# power_v2.net
KiCad netlist of a schematic drawn in EAGLE
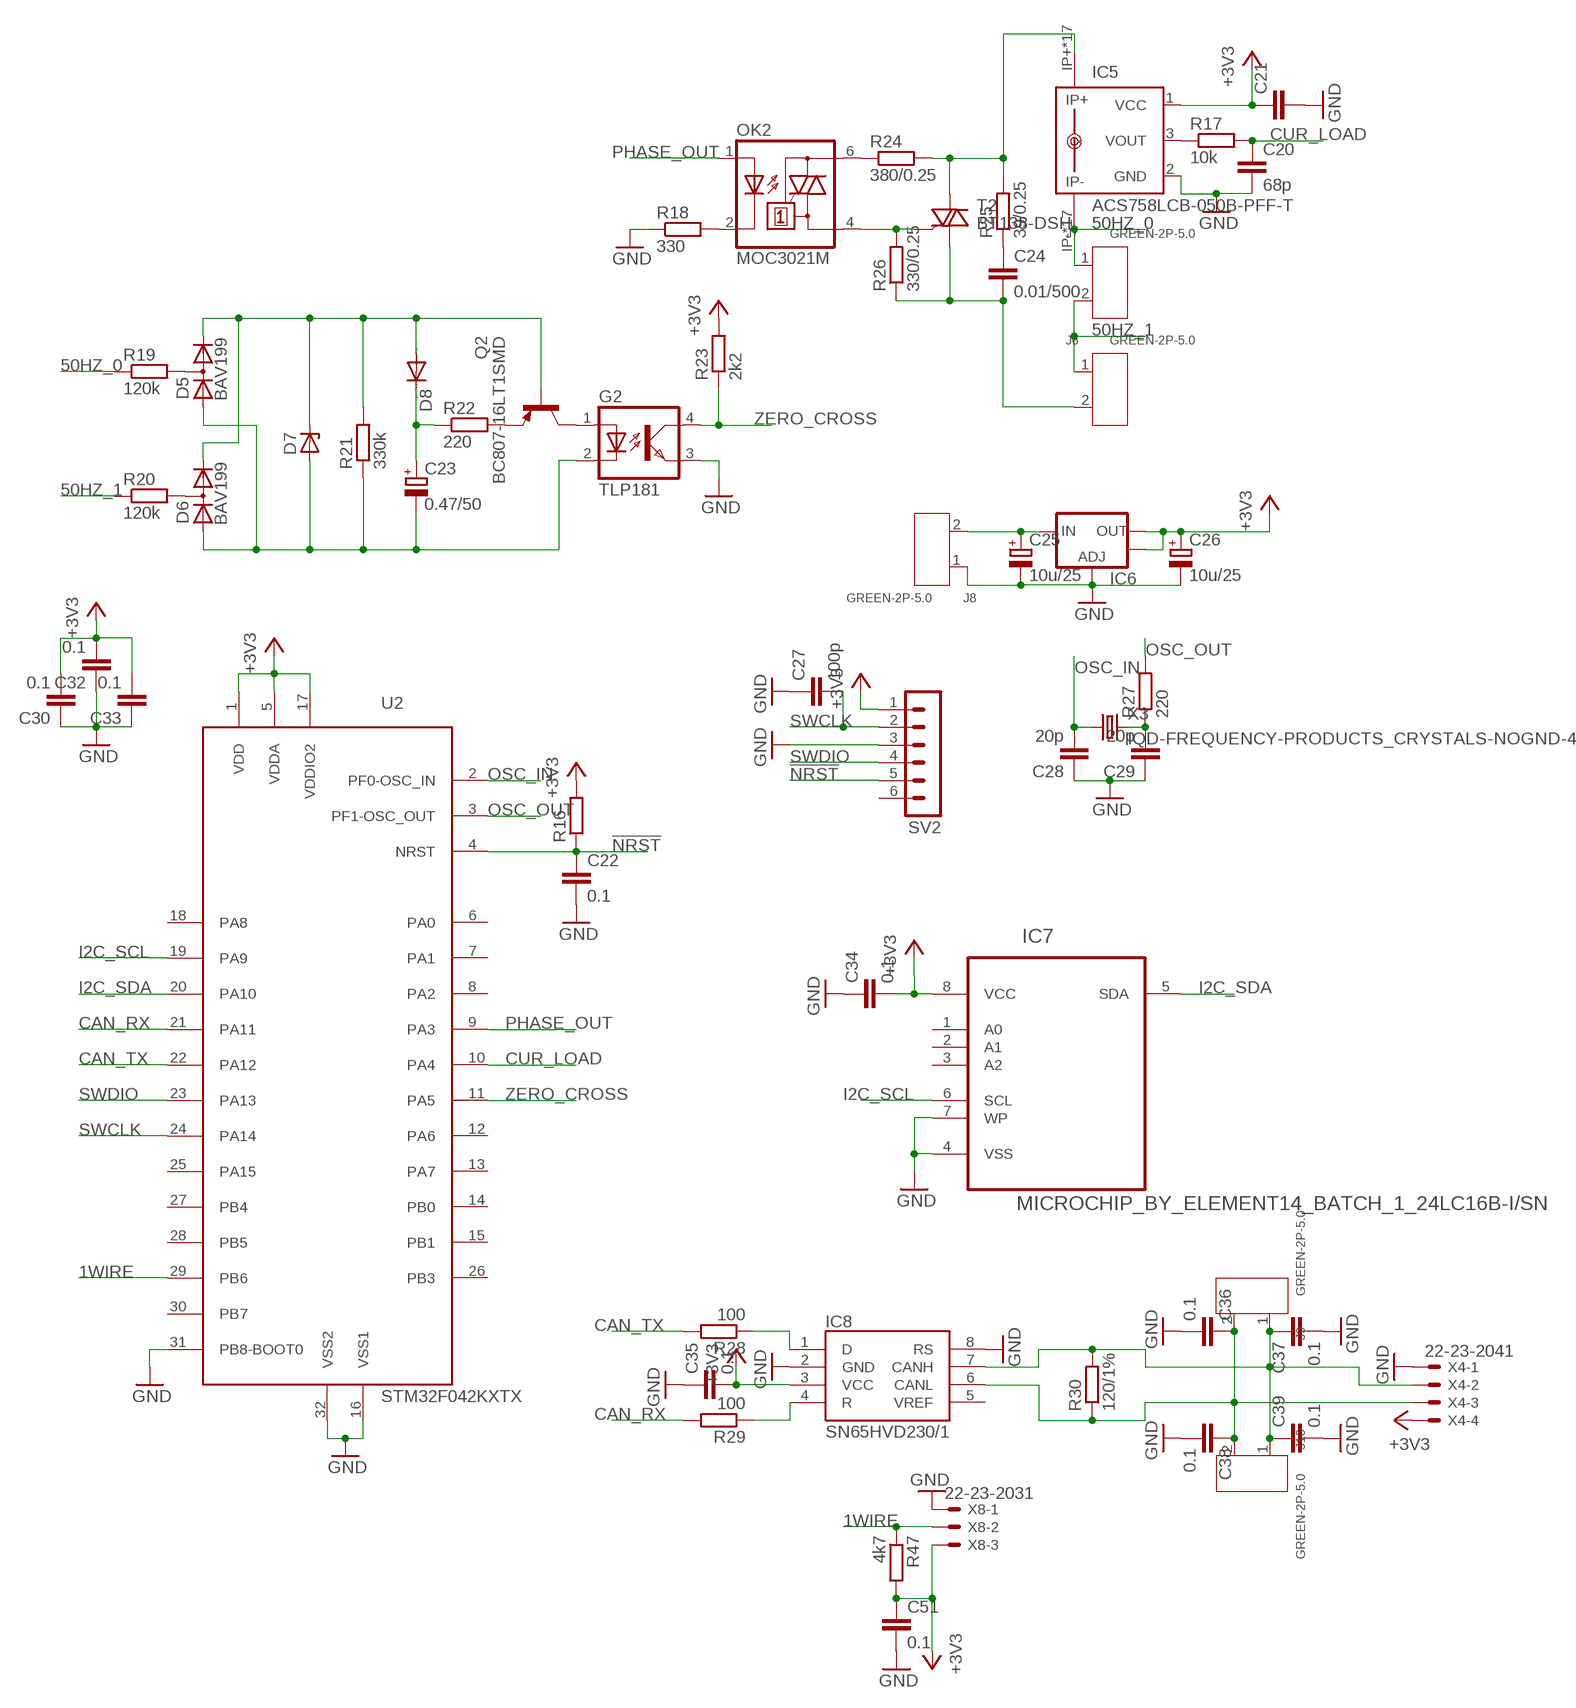
[diagram p0: schematic, sheet 1]

(export (version "E")
  (design (tool "Eeschema 10.0.6"))
  (components
    (comp (ref "C20")
      (value "68p")
      (footprint "eagle-import:C0603")
      (libsource (lib "eagle-import") (part "rcl_334_C-EUC0603"))
    )
    (comp (ref "C21")
      (value "C-EUC0603")
      (footprint "eagle-import:C0603")
      (libsource (lib "eagle-import") (part "C-EUC0603"))
    )
    (comp (ref "C22")
      (value "0.1")
      (footprint "eagle-import:C0603")
      (libsource (lib "eagle-import") (part "C-EUC0603"))
    )
    (comp (ref "C23")
      (value "0.47/50")
      (footprint "eagle-import:C_6032-28R")
      (libsource (lib "eagle-import") (part "CPOL-EUC/6032-28R"))
    )
    (comp (ref "C24")
      (value "0.01/500")
      (footprint "eagle-import:C1206")
      (libsource (lib "eagle-import") (part "C-EUC1206"))
    )
    (comp (ref "C25")
      (value "10u/25")
      (footprint "eagle-import:SMC_B")
      (libsource (lib "eagle-import") (part "CPOL-EUSMCB"))
    )
    (comp (ref "C26")
      (value "10u/25")
      (footprint "eagle-import:SMC_B")
      (libsource (lib "eagle-import") (part "CPOL-EUSMCB"))
    )
    (comp (ref "C27")
      (value "100p")
      (footprint "eagle-import:C0603")
      (libsource (lib "eagle-import") (part "C-EUC0603"))
    )
    (comp (ref "C28")
      (value "20p")
      (footprint "eagle-import:C0603")
      (libsource (lib "eagle-import") (part "C-EUC0603"))
    )
    (comp (ref "C29")
      (value "20p")
      (footprint "eagle-import:C0603")
      (libsource (lib "eagle-import") (part "C-EUC0603"))
    )
    (comp (ref "C30")
      (value "0.1")
      (footprint "eagle-import:C0603")
      (libsource (lib "eagle-import") (part "rcl_334_C-EUC0603"))
    )
    (comp (ref "C32")
      (value "0.1")
      (footprint "eagle-import:C0603")
      (libsource (lib "eagle-import") (part "C-EUC0603"))
    )
    (comp (ref "C33")
      (value "0.1")
      (footprint "eagle-import:C0603")
      (libsource (lib "eagle-import") (part "C-EUC0603"))
    )
    (comp (ref "C34")
      (value "0.1")
      (footprint "eagle-import:C0603")
      (libsource (lib "eagle-import") (part "C-EUC0603"))
    )
    (comp (ref "C35")
      (value "0.1")
      (footprint "eagle-import:C0603")
      (libsource (lib "eagle-import") (part "C-EUC0603"))
    )
    (comp (ref "C36")
      (value "0.1")
      (footprint "eagle-import:C0603")
      (libsource (lib "eagle-import") (part "C-EUC0603"))
    )
    (comp (ref "C37")
      (value "0.1")
      (footprint "eagle-import:C0603")
      (libsource (lib "eagle-import") (part "C-EUC0603"))
    )
    (comp (ref "C38")
      (value "0.1")
      (footprint "eagle-import:C0603")
      (libsource (lib "eagle-import") (part "C-EUC0603"))
    )
    (comp (ref "C39")
      (value "0.1")
      (footprint "eagle-import:C0603")
      (libsource (lib "eagle-import") (part "C-EUC0603"))
    )
    (comp (ref "C51")
      (value "0.1")
      (footprint "eagle-import:C0603")
      (libsource (lib "eagle-import") (part "C-EUC0603"))
    )
    (comp (ref "D5")
      (value "BAV199")
      (footprint "eagle-import:SOT23")
      (libsource (lib "eagle-import") (part "BAV199"))
    )
    (comp (ref "D6")
      (value "BAV199")
      (footprint "eagle-import:SOT23")
      (libsource (lib "eagle-import") (part "BAV199"))
    )
    (comp (ref "D7")
      (value "ZENER-DIODESOD80C")
      (footprint "eagle-import:SOD80C")
      (libsource (lib "eagle-import") (part "ZENER-DIODESOD80C"))
    )
    (comp (ref "D8")
      (value "DIODE-SOD523")
      (footprint "eagle-import:SOD523")
      (libsource (lib "eagle-import") (part "DIODE-SOD523"))
    )
    (comp (ref "G2")
      (value "TLP181")
      (footprint "eagle-import:SOP04")
      (libsource (lib "eagle-import") (part "TLP181"))
    )
    (comp (ref "IC5")
      (value "ACS758LCB-050B-PFF-T")
      (footprint "eagle-import:CB-PFF")
      (libsource (lib "eagle-import") (part "ACS758LCB-050B-PFF-T"))
    )
    (comp (ref "IC6")
      (value "V_REG_LM1117SOT223")
      (footprint "eagle-import:SOT223")
      (libsource (lib "eagle-import") (part "V_REG_LM1117SOT223"))
    )
    (comp (ref "IC7")
      (value "MICROCHIP_BY_ELEMENT14_BATCH_1_24LC16B-I/SN")
      (footprint "eagle-import:MICROCHIP_BY_ELEMENT14_BATCH_1_SOIC127P600X175-8N")
      (fields (field (name "MPN") "24LC16B-I/SN"))
      (libsource (lib "eagle-import") (part "MICROCHIP_BY_ELEMENT14_BATCH_1_24LC16B-I/SN"))
    )
    (comp (ref "IC8")
      (value "SN65HVD230/1")
      (footprint "eagle-import:SO8")
      (libsource (lib "eagle-import") (part "SN65HVD230/1"))
    )
    (comp (ref "J6")
      (value "GREEN-2P-5.0")
      (footprint "eagle-import:H2-5.0-10.5X8.0MM")
      (libsource (lib "eagle-import") (part "SCREW-TERMINAL-GREEN(2P-5.0)"))
    )
    (comp (ref "J7")
      (value "GREEN-2P-5.0")
      (footprint "eagle-import:H2-5.0-10.5X8.0MM")
      (libsource (lib "eagle-import") (part "SCREW-TERMINAL-GREEN(2P-5.0)"))
    )
    (comp (ref "J8")
      (value "GREEN-2P-5.0")
      (footprint "eagle-import:H2-5.0-10.5X8.0MM")
      (libsource (lib "eagle-import") (part "SCREW-TERMINAL-GREEN(2P-5.0)"))
    )
    (comp (ref "J9")
      (value "GREEN-2P-5.0")
      (footprint "eagle-import:H2-5.0-10.5X8.0MM")
      (libsource (lib "eagle-import") (part "SCREW-TERMINAL-GREEN(2P-5.0)"))
    )
    (comp (ref "J10")
      (value "GREEN-2P-5.0")
      (footprint "eagle-import:H2-5.0-10.5X8.0MM")
      (libsource (lib "eagle-import") (part "SCREW-TERMINAL-GREEN(2P-5.0)"))
    )
    (comp (ref "OK2")
      (value "MOC3021M")
      (footprint "eagle-import:DIL06")
      (fields (field (name "MF") "FAIRCHILD SEMICONDUCTOR") (field (name "MPN") "MOC3021-M"))
      (libsource (lib "eagle-import") (part "MOC30M21"))
    )
    (comp (ref "Q2")
      (value "BC807-16LT1SMD")
      (footprint "eagle-import:SOT23-BEC")
      (libsource (lib "eagle-import") (part "BC807SMD-16LT1"))
    )
    (comp (ref "R16")
      (value "R-EU_R0603")
      (footprint "eagle-import:R0603")
      (libsource (lib "eagle-import") (part "R-EU_R0603"))
    )
    (comp (ref "R17")
      (value "10k")
      (footprint "eagle-import:R0603")
      (libsource (lib "eagle-import") (part "R-EU_R0603"))
    )
    (comp (ref "R18")
      (value "330")
      (footprint "eagle-import:R0603")
      (libsource (lib "eagle-import") (part "rcl_334_R-EU_R0603"))
    )
    (comp (ref "R19")
      (value "120k")
      (footprint "eagle-import:R1206")
      (libsource (lib "eagle-import") (part "R-EU_R1206"))
    )
    (comp (ref "R20")
      (value "120k")
      (footprint "eagle-import:R1206")
      (libsource (lib "eagle-import") (part "R-EU_R1206"))
    )
    (comp (ref "R21")
      (value "330k")
      (footprint "eagle-import:R1206")
      (libsource (lib "eagle-import") (part "R-EU_R1206"))
    )
    (comp (ref "R22")
      (value "220")
      (footprint "eagle-import:R1206")
      (libsource (lib "eagle-import") (part "R-EU_R1206"))
    )
    (comp (ref "R23")
      (value "2k2")
      (footprint "eagle-import:R0603")
      (libsource (lib "eagle-import") (part "R-EU_R0603"))
    )
    (comp (ref "R24")
      (value "380/0.25")
      (footprint "eagle-import:M1206")
      (libsource (lib "eagle-import") (part "R-EU_M1206"))
    )
    (comp (ref "R25")
      (value "39/0.25")
      (footprint "eagle-import:M1206")
      (libsource (lib "eagle-import") (part "R-EU_M1206"))
    )
    (comp (ref "R26")
      (value "330/0.25")
      (footprint "eagle-import:M1206")
      (libsource (lib "eagle-import") (part "R-EU_M1206"))
    )
    (comp (ref "R27")
      (value "220")
      (footprint "eagle-import:R0603")
      (libsource (lib "eagle-import") (part "R-EU_R0603"))
    )
    (comp (ref "R28")
      (value "100")
      (footprint "eagle-import:R0603")
      (libsource (lib "eagle-import") (part "rcl_334_R-EU_R0603"))
    )
    (comp (ref "R29")
      (value "100")
      (footprint "eagle-import:R0603")
      (libsource (lib "eagle-import") (part "R-EU_R0603"))
    )
    (comp (ref "R30")
      (value "120/1%")
      (footprint "eagle-import:R0603")
      (libsource (lib "eagle-import") (part "R-EU_R0603"))
    )
    (comp (ref "R47")
      (value "4k7")
      (footprint "eagle-import:R0603")
      (libsource (lib "eagle-import") (part "rcl_334_R-EU_R0603"))
    )
    (comp (ref "SV2")
      (value "CON-LSTB_MA06-1")
      (footprint "eagle-import:CON-LSTB_MA06-1")
      (libsource (lib "eagle-import") (part "CON-LSTB_MA06-1"))
    )
    (comp (ref "T2")
      (value "BT138-DSH")
      (footprint "eagle-import:TO220DSH")
      (libsource (lib "eagle-import") (part "BT138-DSH"))
    )
    (comp (ref "U2")
      (value "STM32F042KXTX")
      (footprint "eagle-import:LQFP32")
      (libsource (lib "eagle-import") (part "STM32F042KXTX"))
    )
    (comp (ref "X3")
      (value "IQD-FREQUENCY-PRODUCTS_CRYSTALS-NOGND-4-HSMX")
      (footprint "eagle-import:IQD-FREQUENCY-PRODUCTS_HC49-4-HSMX")
      (libsource (lib "eagle-import") (part "IQD-FREQUENCY-PRODUCTS_CRYSTALS-NOGND-4-HSMX"))
    )
    (comp (ref "X4")
      (value "22-23-2041")
      (footprint "eagle-import:22-23-2041")
      (fields (field (name "MF") "MOLEX"))
      (libsource (lib "eagle-import") (part "22-23-2041"))
    )
    (comp (ref "X8")
      (value "22-23-2031")
      (footprint "eagle-import:22-23-2031")
      (fields (field (name "MF") "MOLEX"))
      (libsource (lib "eagle-import") (part "22-23-2031"))
    )
  )
  (nets
    (net (code "1") (name "+3V3") (class "Default")
      (node (ref "C21") (pin "1") (pinfunction "1_1") (pintype "passive"))
      (node (ref "C26") (pin "+") (pinfunction "+_+") (pintype "passive"))
      (node (ref "C30") (pin "2") (pinfunction "2_2") (pintype "passive"))
      (node (ref "C32") (pin "2") (pinfunction "2_2") (pintype "passive"))
      (node (ref "C33") (pin "2") (pinfunction "2_2") (pintype "passive"))
      (node (ref "C34") (pin "2") (pinfunction "2_2") (pintype "passive"))
      (node (ref "C35") (pin "2") (pinfunction "2_2") (pintype "passive"))
      (node (ref "C51") (pin "1") (pinfunction "1_1") (pintype "passive"))
      (node (ref "IC5") (pin "1") (pinfunction "VCC_1") (pintype "power_in"))
      (node (ref "IC6") (pin "2") (pinfunction "OUT_2") (pintype "output"))
      (node (ref "IC6") (pin "4") (pinfunction "OUT_4") (pintype "output"))
      (node (ref "IC7") (pin "8") (pinfunction "VCC_8") (pintype "power_in"))
      (node (ref "IC8") (pin "3") (pinfunction "VCC_3") (pintype "power_in"))
      (node (ref "R16") (pin "2") (pinfunction "2_2") (pintype "passive"))
      (node (ref "R23") (pin "2") (pinfunction "2_2") (pintype "passive"))
      (node (ref "R47") (pin "2") (pinfunction "2_2") (pintype "passive"))
      (node (ref "SV2") (pin "1") (pinfunction "1_1") (pintype "passive"))
      (node (ref "U2") (pin "1") (pinfunction "VDD_1") (pintype "bidirectional"))
      (node (ref "U2") (pin "17") (pinfunction "VDDIO2_17") (pintype "bidirectional"))
      (node (ref "U2") (pin "5") (pinfunction "VDDA_5") (pintype "bidirectional"))
      (node (ref "X4") (pin "4") (pinfunction "S_4") (pintype "passive"))
      (node (ref "X8") (pin "3") (pinfunction "S_3") (pintype "passive"))
    )
    (net (code "2") (name "/1WIRE") (class "Default")
      (node (ref "R47") (pin "1") (pinfunction "1_1") (pintype "passive"))
      (node (ref "U2") (pin "29") (pinfunction "PB6_29") (pintype "bidirectional"))
      (node (ref "X8") (pin "2") (pinfunction "S_2") (pintype "passive"))
    )
    (net (code "3") (name "/50HZ_0") (class "Default")
      (node (ref "IC5") (pin "IP-") (pinfunction "IP-_IP-") (pintype "passive"))
      (node (ref "IC5") (pin "IP-@10") (pinfunction "IP-_IP-@10") (pintype "passive"))
      (node (ref "IC5") (pin "IP-@11") (pinfunction "IP-_IP-@11") (pintype "passive"))
      (node (ref "IC5") (pin "IP-@12") (pinfunction "IP-_IP-@12") (pintype "passive"))
      (node (ref "IC5") (pin "IP-@13") (pinfunction "IP-_IP-@13") (pintype "passive"))
      (node (ref "IC5") (pin "IP-@14") (pinfunction "IP-_IP-@14") (pintype "passive"))
      (node (ref "IC5") (pin "IP-@15") (pinfunction "IP-_IP-@15") (pintype "passive"))
      (node (ref "IC5") (pin "IP-@16") (pinfunction "IP-_IP-@16") (pintype "passive"))
      (node (ref "IC5") (pin "IP-@17") (pinfunction "IP-_IP-@17") (pintype "passive"))
      (node (ref "IC5") (pin "IP-@2") (pinfunction "IP-_IP-@2") (pintype "passive"))
      (node (ref "IC5") (pin "IP-@3") (pinfunction "IP-_IP-@3") (pintype "passive"))
      (node (ref "IC5") (pin "IP-@4") (pinfunction "IP-_IP-@4") (pintype "passive"))
      (node (ref "IC5") (pin "IP-@5") (pinfunction "IP-_IP-@5") (pintype "passive"))
      (node (ref "IC5") (pin "IP-@6") (pinfunction "IP-_IP-@6") (pintype "passive"))
      (node (ref "IC5") (pin "IP-@7") (pinfunction "IP-_IP-@7") (pintype "passive"))
      (node (ref "IC5") (pin "IP-@8") (pinfunction "IP-_IP-@8") (pintype "passive"))
      (node (ref "IC5") (pin "IP-@9") (pinfunction "IP-_IP-@9") (pintype "passive"))
      (node (ref "J7") (pin "1") (pinfunction "1_1") (pintype "bidirectional"))
      (node (ref "R19") (pin "1") (pinfunction "1_1") (pintype "passive"))
    )
    (net (code "4") (name "/50HZ_1") (class "Default")
      (node (ref "J6") (pin "1") (pinfunction "1_1") (pintype "bidirectional"))
      (node (ref "J7") (pin "2") (pinfunction "2_2") (pintype "bidirectional"))
      (node (ref "R20") (pin "1") (pinfunction "1_1") (pintype "passive"))
    )
    (net (code "5") (name "/CAN_RX") (class "Default")
      (node (ref "R29") (pin "2") (pinfunction "2_2") (pintype "passive"))
      (node (ref "U2") (pin "21") (pinfunction "PA11_21") (pintype "bidirectional"))
    )
    (net (code "6") (name "/CAN_TX") (class "Default")
      (node (ref "R28") (pin "2") (pinfunction "2_2") (pintype "passive"))
      (node (ref "U2") (pin "22") (pinfunction "PA12_22") (pintype "bidirectional"))
    )
    (net (code "7") (name "/CUR_LOAD") (class "Default")
      (node (ref "C20") (pin "1") (pinfunction "1_1") (pintype "passive"))
      (node (ref "R17") (pin "2") (pinfunction "2_2") (pintype "passive"))
      (node (ref "U2") (pin "10") (pinfunction "PA4_10") (pintype "bidirectional"))
    )
    (net (code "8") (name "/I2C_SCL") (class "Default")
      (node (ref "IC7") (pin "6") (pinfunction "SCL_6") (pintype "input"))
      (node (ref "U2") (pin "19") (pinfunction "PA9_19") (pintype "bidirectional"))
    )
    (net (code "9") (name "/I2C_SDA") (class "Default")
      (node (ref "IC7") (pin "5") (pinfunction "SDA_5") (pintype "bidirectional"))
      (node (ref "U2") (pin "20") (pinfunction "PA10_20") (pintype "bidirectional"))
    )
    (net (code "10") (name "/OSC_IN") (class "Default")
      (node (ref "C28") (pin "2") (pinfunction "2_2") (pintype "passive"))
      (node (ref "U2") (pin "2") (pinfunction "PF0-OSC_IN_2") (pintype "bidirectional"))
      (node (ref "X3") (pin "1") (pinfunction "1_1") (pintype "passive"))
    )
    (net (code "11") (name "/OSC_OUT") (class "Default")
      (node (ref "R27") (pin "2") (pinfunction "2_2") (pintype "passive"))
      (node (ref "U2") (pin "3") (pinfunction "PF1-OSC_OUT_3") (pintype "bidirectional"))
    )
    (net (code "12") (name "/PHASE_OUT") (class "Default")
      (node (ref "OK2") (pin "1") (pinfunction "A_1") (pintype "passive"))
      (node (ref "U2") (pin "9") (pinfunction "PA3_9") (pintype "bidirectional"))
    )
    (net (code "13") (name "/SWCLK") (class "Default")
      (node (ref "C27") (pin "2") (pinfunction "2_2") (pintype "passive"))
      (node (ref "SV2") (pin "2") (pinfunction "2_2") (pintype "passive"))
      (node (ref "U2") (pin "24") (pinfunction "PA14_24") (pintype "bidirectional"))
    )
    (net (code "14") (name "/SWDIO") (class "Default")
      (node (ref "SV2") (pin "4") (pinfunction "4_4") (pintype "passive"))
      (node (ref "U2") (pin "23") (pinfunction "PA13_23") (pintype "bidirectional"))
    )
    (net (code "15") (name "/ZERO_CROSS") (class "Default")
      (node (ref "G2") (pin "4") (pinfunction "COL_4") (pintype "passive"))
      (node (ref "R23") (pin "1") (pinfunction "1_1") (pintype "passive"))
      (node (ref "U2") (pin "11") (pinfunction "PA5_11") (pintype "bidirectional"))
    )
    (net (code "16") (name "/~{NRST}") (class "Default")
      (node (ref "C22") (pin "1") (pinfunction "1_1") (pintype "passive"))
      (node (ref "R16") (pin "1") (pinfunction "1_1") (pintype "passive"))
      (node (ref "SV2") (pin "5") (pinfunction "5_5") (pintype "passive"))
      (node (ref "U2") (pin "4") (pinfunction "NRST_4") (pintype "bidirectional"))
    )
    (net (code "17") (name "GND") (class "Default")
      (node (ref "C20") (pin "2") (pinfunction "2_2") (pintype "passive"))
      (node (ref "C21") (pin "2") (pinfunction "2_2") (pintype "passive"))
      (node (ref "C22") (pin "2") (pinfunction "2_2") (pintype "passive"))
      (node (ref "C25") (pin "-") (pinfunction "-_-") (pintype "passive"))
      (node (ref "C26") (pin "-") (pinfunction "-_-") (pintype "passive"))
      (node (ref "C27") (pin "1") (pinfunction "1_1") (pintype "passive"))
      (node (ref "C28") (pin "1") (pinfunction "1_1") (pintype "passive"))
      (node (ref "C29") (pin "1") (pinfunction "1_1") (pintype "passive"))
      (node (ref "C30") (pin "1") (pinfunction "1_1") (pintype "passive"))
      (node (ref "C32") (pin "1") (pinfunction "1_1") (pintype "passive"))
      (node (ref "C33") (pin "1") (pinfunction "1_1") (pintype "passive"))
      (node (ref "C34") (pin "1") (pinfunction "1_1") (pintype "passive"))
      (node (ref "C35") (pin "1") (pinfunction "1_1") (pintype "passive"))
      (node (ref "C36") (pin "2") (pinfunction "2_2") (pintype "passive"))
      (node (ref "C37") (pin "2") (pinfunction "2_2") (pintype "passive"))
      (node (ref "C38") (pin "2") (pinfunction "2_2") (pintype "passive"))
      (node (ref "C39") (pin "2") (pinfunction "2_2") (pintype "passive"))
      (node (ref "C51") (pin "2") (pinfunction "2_2") (pintype "passive"))
      (node (ref "G2") (pin "3") (pinfunction "EMIT_3") (pintype "passive"))
      (node (ref "IC5") (pin "2") (pinfunction "GND_2") (pintype "power_in"))
      (node (ref "IC6") (pin "1") (pinfunction "ADJ_1") (pintype "input"))
      (node (ref "IC7") (pin "4") (pinfunction "VSS_4") (pintype "passive"))
      (node (ref "IC7") (pin "7") (pinfunction "WP_7") (pintype "input"))
      (node (ref "IC8") (pin "2") (pinfunction "GND_2") (pintype "power_in"))
      (node (ref "IC8") (pin "8") (pinfunction "RS_8") (pintype "bidirectional"))
      (node (ref "J8") (pin "1") (pinfunction "1_1") (pintype "bidirectional"))
      (node (ref "R18") (pin "1") (pinfunction "1_1") (pintype "passive"))
      (node (ref "SV2") (pin "3") (pinfunction "3_3") (pintype "passive"))
      (node (ref "U2") (pin "16") (pinfunction "VSS1_16") (pintype "bidirectional"))
      (node (ref "U2") (pin "31") (pinfunction "PB8-BOOT0_31") (pintype "bidirectional"))
      (node (ref "U2") (pin "32") (pinfunction "VSS2_32") (pintype "bidirectional"))
      (node (ref "X4") (pin "1") (pinfunction "S_1") (pintype "passive"))
      (node (ref "X8") (pin "1") (pinfunction "S_1") (pintype "passive"))
    )
    (net (code "18") (name "Net-(C23-Pad+)") (class "Default")
      (node (ref "C23") (pin "+") (pinfunction "+_+") (pintype "passive"))
      (node (ref "D8") (pin "C") (pinfunction "C_C") (pintype "passive"))
      (node (ref "R22") (pin "1") (pinfunction "1_1") (pintype "passive"))
    )
    (net (code "19") (name "Net-(C24-Pad1)") (class "Default")
      (node (ref "C24") (pin "1") (pinfunction "1_1") (pintype "passive"))
      (node (ref "R25") (pin "1") (pinfunction "1_1") (pintype "passive"))
    )
    (net (code "20") (name "Net-(C24-Pad2)") (class "Default")
      (node (ref "C24") (pin "2") (pinfunction "2_2") (pintype "passive"))
      (node (ref "J6") (pin "2") (pinfunction "2_2") (pintype "bidirectional"))
      (node (ref "R26") (pin "1") (pinfunction "1_1") (pintype "passive"))
      (node (ref "T2") (pin "A1") (pinfunction "A1_A1") (pintype "passive"))
    )
    (net (code "21") (name "Net-(C29-Pad2)") (class "Default")
      (node (ref "C29") (pin "2") (pinfunction "2_2") (pintype "passive"))
      (node (ref "R27") (pin "1") (pinfunction "1_1") (pintype "passive"))
      (node (ref "X3") (pin "2") (pinfunction "2_2") (pintype "passive"))
    )
    (net (code "22") (name "Net-(D5-A)") (class "Default")
      (node (ref "C23") (pin "-") (pinfunction "-_-") (pintype "passive"))
      (node (ref "D5") (pin "1") (pinfunction "A_1") (pintype "passive"))
      (node (ref "D6") (pin "1") (pinfunction "A_1") (pintype "passive"))
      (node (ref "D7") (pin "A") (pinfunction "A_A") (pintype "passive"))
      (node (ref "G2") (pin "2") (pinfunction "C_2") (pintype "passive"))
      (node (ref "R21") (pin "1") (pinfunction "1_1") (pintype "passive"))
    )
    (net (code "23") (name "Net-(D5-AC)") (class "Default")
      (node (ref "D5") (pin "3") (pinfunction "AC_3") (pintype "passive"))
      (node (ref "R19") (pin "2") (pinfunction "2_2") (pintype "passive"))
    )
    (net (code "24") (name "Net-(D5-C)") (class "Default")
      (node (ref "D5") (pin "2") (pinfunction "C_2") (pintype "passive"))
      (node (ref "D6") (pin "2") (pinfunction "C_2") (pintype "passive"))
      (node (ref "D7") (pin "C") (pinfunction "C_C") (pintype "passive"))
      (node (ref "D8") (pin "A") (pinfunction "A_A") (pintype "passive"))
      (node (ref "Q2") (pin "B") (pinfunction "B_B") (pintype "passive"))
      (node (ref "R21") (pin "2") (pinfunction "2_2") (pintype "passive"))
    )
    (net (code "25") (name "Net-(D6-AC)") (class "Default")
      (node (ref "D6") (pin "3") (pinfunction "AC_3") (pintype "passive"))
      (node (ref "R20") (pin "2") (pinfunction "2_2") (pintype "passive"))
    )
    (net (code "26") (name "Net-(G2-A)") (class "Default")
      (node (ref "G2") (pin "1") (pinfunction "A_1") (pintype "passive"))
      (node (ref "Q2") (pin "C") (pinfunction "C_C") (pintype "passive"))
    )
    (net (code "27") (name "Net-(IC5-IP+-PadIP+@10)") (class "Default")
      (node (ref "IC5") (pin "IP+") (pinfunction "IP+_IP+") (pintype "passive"))
      (node (ref "IC5") (pin "IP+@10") (pinfunction "IP+_IP+@10") (pintype "passive"))
      (node (ref "IC5") (pin "IP+@11") (pinfunction "IP+_IP+@11") (pintype "passive"))
      (node (ref "IC5") (pin "IP+@12") (pinfunction "IP+_IP+@12") (pintype "passive"))
      (node (ref "IC5") (pin "IP+@13") (pinfunction "IP+_IP+@13") (pintype "passive"))
      (node (ref "IC5") (pin "IP+@14") (pinfunction "IP+_IP+@14") (pintype "passive"))
      (node (ref "IC5") (pin "IP+@15") (pinfunction "IP+_IP+@15") (pintype "passive"))
      (node (ref "IC5") (pin "IP+@16") (pinfunction "IP+_IP+@16") (pintype "passive"))
      (node (ref "IC5") (pin "IP+@17") (pinfunction "IP+_IP+@17") (pintype "passive"))
      (node (ref "IC5") (pin "IP+@2") (pinfunction "IP+_IP+@2") (pintype "passive"))
      (node (ref "IC5") (pin "IP+@3") (pinfunction "IP+_IP+@3") (pintype "passive"))
      (node (ref "IC5") (pin "IP+@4") (pinfunction "IP+_IP+@4") (pintype "passive"))
      (node (ref "IC5") (pin "IP+@5") (pinfunction "IP+_IP+@5") (pintype "passive"))
      (node (ref "IC5") (pin "IP+@6") (pinfunction "IP+_IP+@6") (pintype "passive"))
      (node (ref "IC5") (pin "IP+@7") (pinfunction "IP+_IP+@7") (pintype "passive"))
      (node (ref "IC5") (pin "IP+@8") (pinfunction "IP+_IP+@8") (pintype "passive"))
      (node (ref "IC5") (pin "IP+@9") (pinfunction "IP+_IP+@9") (pintype "passive"))
      (node (ref "R24") (pin "2") (pinfunction "2_2") (pintype "passive"))
      (node (ref "R25") (pin "2") (pinfunction "2_2") (pintype "passive"))
      (node (ref "T2") (pin "A2") (pinfunction "A2_A2") (pintype "passive"))
    )
    (net (code "28") (name "Net-(IC5-VOUT)") (class "Default")
      (node (ref "IC5") (pin "3") (pinfunction "VOUT_3") (pintype "output"))
      (node (ref "R17") (pin "1") (pinfunction "1_1") (pintype "passive"))
    )
    (net (code "29") (name "Net-(IC6-IN)") (class "Default")
      (node (ref "C25") (pin "+") (pinfunction "+_+") (pintype "passive"))
      (node (ref "IC6") (pin "3") (pinfunction "IN_3") (pintype "input"))
      (node (ref "J8") (pin "2") (pinfunction "2_2") (pintype "bidirectional"))
    )
    (net (code "30") (name "Net-(IC8-CANH)") (class "Default")
      (node (ref "C37") (pin "1") (pinfunction "1_1") (pintype "passive"))
      (node (ref "C39") (pin "1") (pinfunction "1_1") (pintype "passive"))
      (node (ref "IC8") (pin "7") (pinfunction "CANH_7") (pintype "bidirectional"))
      (node (ref "J10") (pin "1") (pinfunction "1_1") (pintype "bidirectional"))
      (node (ref "J9") (pin "1") (pinfunction "1_1") (pintype "bidirectional"))
      (node (ref "R30") (pin "2") (pinfunction "2_2") (pintype "passive"))
      (node (ref "X4") (pin "2") (pinfunction "S_2") (pintype "passive"))
    )
    (net (code "31") (name "Net-(IC8-CANL)") (class "Default")
      (node (ref "C36") (pin "1") (pinfunction "1_1") (pintype "passive"))
      (node (ref "C38") (pin "1") (pinfunction "1_1") (pintype "passive"))
      (node (ref "IC8") (pin "6") (pinfunction "CANL_6") (pintype "bidirectional"))
      (node (ref "J10") (pin "2") (pinfunction "2_2") (pintype "bidirectional"))
      (node (ref "J9") (pin "2") (pinfunction "2_2") (pintype "bidirectional"))
      (node (ref "R30") (pin "1") (pinfunction "1_1") (pintype "passive"))
      (node (ref "X4") (pin "3") (pinfunction "S_3") (pintype "passive"))
    )
    (net (code "32") (name "Net-(IC8-D)") (class "Default")
      (node (ref "IC8") (pin "1") (pinfunction "D_1") (pintype "bidirectional"))
      (node (ref "R28") (pin "1") (pinfunction "1_1") (pintype "passive"))
    )
    (net (code "33") (name "Net-(IC8-R)") (class "Default")
      (node (ref "IC8") (pin "4") (pinfunction "R_4") (pintype "bidirectional"))
      (node (ref "R29") (pin "1") (pinfunction "1_1") (pintype "passive"))
    )
    (net (code "34") (name "Net-(OK2-A1)") (class "Default")
      (node (ref "OK2") (pin "4") (pinfunction "A1_4") (pintype "passive"))
      (node (ref "R26") (pin "2") (pinfunction "2_2") (pintype "passive"))
      (node (ref "T2") (pin "G") (pinfunction "G_G") (pintype "passive"))
    )
    (net (code "35") (name "Net-(OK2-A2)") (class "Default")
      (node (ref "OK2") (pin "6") (pinfunction "A2_6") (pintype "passive"))
      (node (ref "R24") (pin "1") (pinfunction "1_1") (pintype "passive"))
    )
    (net (code "36") (name "Net-(OK2-C)") (class "Default")
      (node (ref "OK2") (pin "2") (pinfunction "C_2") (pintype "passive"))
      (node (ref "R18") (pin "2") (pinfunction "2_2") (pintype "passive"))
    )
    (net (code "37") (name "Net-(Q2-PadE)") (class "Default")
      (node (ref "Q2") (pin "E") (pinfunction "E_E") (pintype "passive"))
      (node (ref "R22") (pin "2") (pinfunction "2_2") (pintype "passive"))
    )
    (net (code "38") (name "unconnected-(IC7-A0-Pad1)") (class "Default")
      (node (ref "IC7") (pin "1") (pinfunction "A0_1") (pintype "input"))
    )
    (net (code "39") (name "unconnected-(IC7-A1-Pad2)") (class "Default")
      (node (ref "IC7") (pin "2") (pinfunction "A1_2") (pintype "input"))
    )
    (net (code "40") (name "unconnected-(IC7-A2-Pad3)") (class "Default")
      (node (ref "IC7") (pin "3") (pinfunction "A2_3") (pintype "input"))
    )
    (net (code "41") (name "unconnected-(IC8-VREF-Pad5)") (class "Default")
      (node (ref "IC8") (pin "5") (pinfunction "VREF_5") (pintype "bidirectional"))
    )
    (net (code "42") (name "unconnected-(SV2-Pad6)") (class "Default")
      (node (ref "SV2") (pin "6") (pinfunction "6_6") (pintype "passive"))
    )
    (net (code "43") (name "unconnected-(U2-PA0-Pad6)") (class "Default")
      (node (ref "U2") (pin "6") (pinfunction "PA0_6") (pintype "bidirectional"))
    )
    (net (code "44") (name "unconnected-(U2-PA1-Pad7)") (class "Default")
      (node (ref "U2") (pin "7") (pinfunction "PA1_7") (pintype "bidirectional"))
    )
    (net (code "45") (name "unconnected-(U2-PA2-Pad8)") (class "Default")
      (node (ref "U2") (pin "8") (pinfunction "PA2_8") (pintype "bidirectional"))
    )
    (net (code "46") (name "unconnected-(U2-PA6-Pad12)") (class "Default")
      (node (ref "U2") (pin "12") (pinfunction "PA6_12") (pintype "bidirectional"))
    )
    (net (code "47") (name "unconnected-(U2-PA7-Pad13)") (class "Default")
      (node (ref "U2") (pin "13") (pinfunction "PA7_13") (pintype "bidirectional"))
    )
    (net (code "48") (name "unconnected-(U2-PA8-Pad18)") (class "Default")
      (node (ref "U2") (pin "18") (pinfunction "PA8_18") (pintype "bidirectional"))
    )
    (net (code "49") (name "unconnected-(U2-PA15-Pad25)") (class "Default")
      (node (ref "U2") (pin "25") (pinfunction "PA15_25") (pintype "bidirectional"))
    )
    (net (code "50") (name "unconnected-(U2-PB0-Pad14)") (class "Default")
      (node (ref "U2") (pin "14") (pinfunction "PB0_14") (pintype "bidirectional"))
    )
    (net (code "51") (name "unconnected-(U2-PB1-Pad15)") (class "Default")
      (node (ref "U2") (pin "15") (pinfunction "PB1_15") (pintype "bidirectional"))
    )
    (net (code "52") (name "unconnected-(U2-PB3-Pad26)") (class "Default")
      (node (ref "U2") (pin "26") (pinfunction "PB3_26") (pintype "bidirectional"))
    )
    (net (code "53") (name "unconnected-(U2-PB4-Pad27)") (class "Default")
      (node (ref "U2") (pin "27") (pinfunction "PB4_27") (pintype "bidirectional"))
    )
    (net (code "54") (name "unconnected-(U2-PB5-Pad28)") (class "Default")
      (node (ref "U2") (pin "28") (pinfunction "PB5_28") (pintype "bidirectional"))
    )
    (net (code "55") (name "unconnected-(U2-PB7-Pad30)") (class "Default")
      (node (ref "U2") (pin "30") (pinfunction "PB7_30") (pintype "bidirectional"))
    )
  )
)
